# IMU_Layer_final.net
KiCad netlist of a schematic drawn in EAGLE
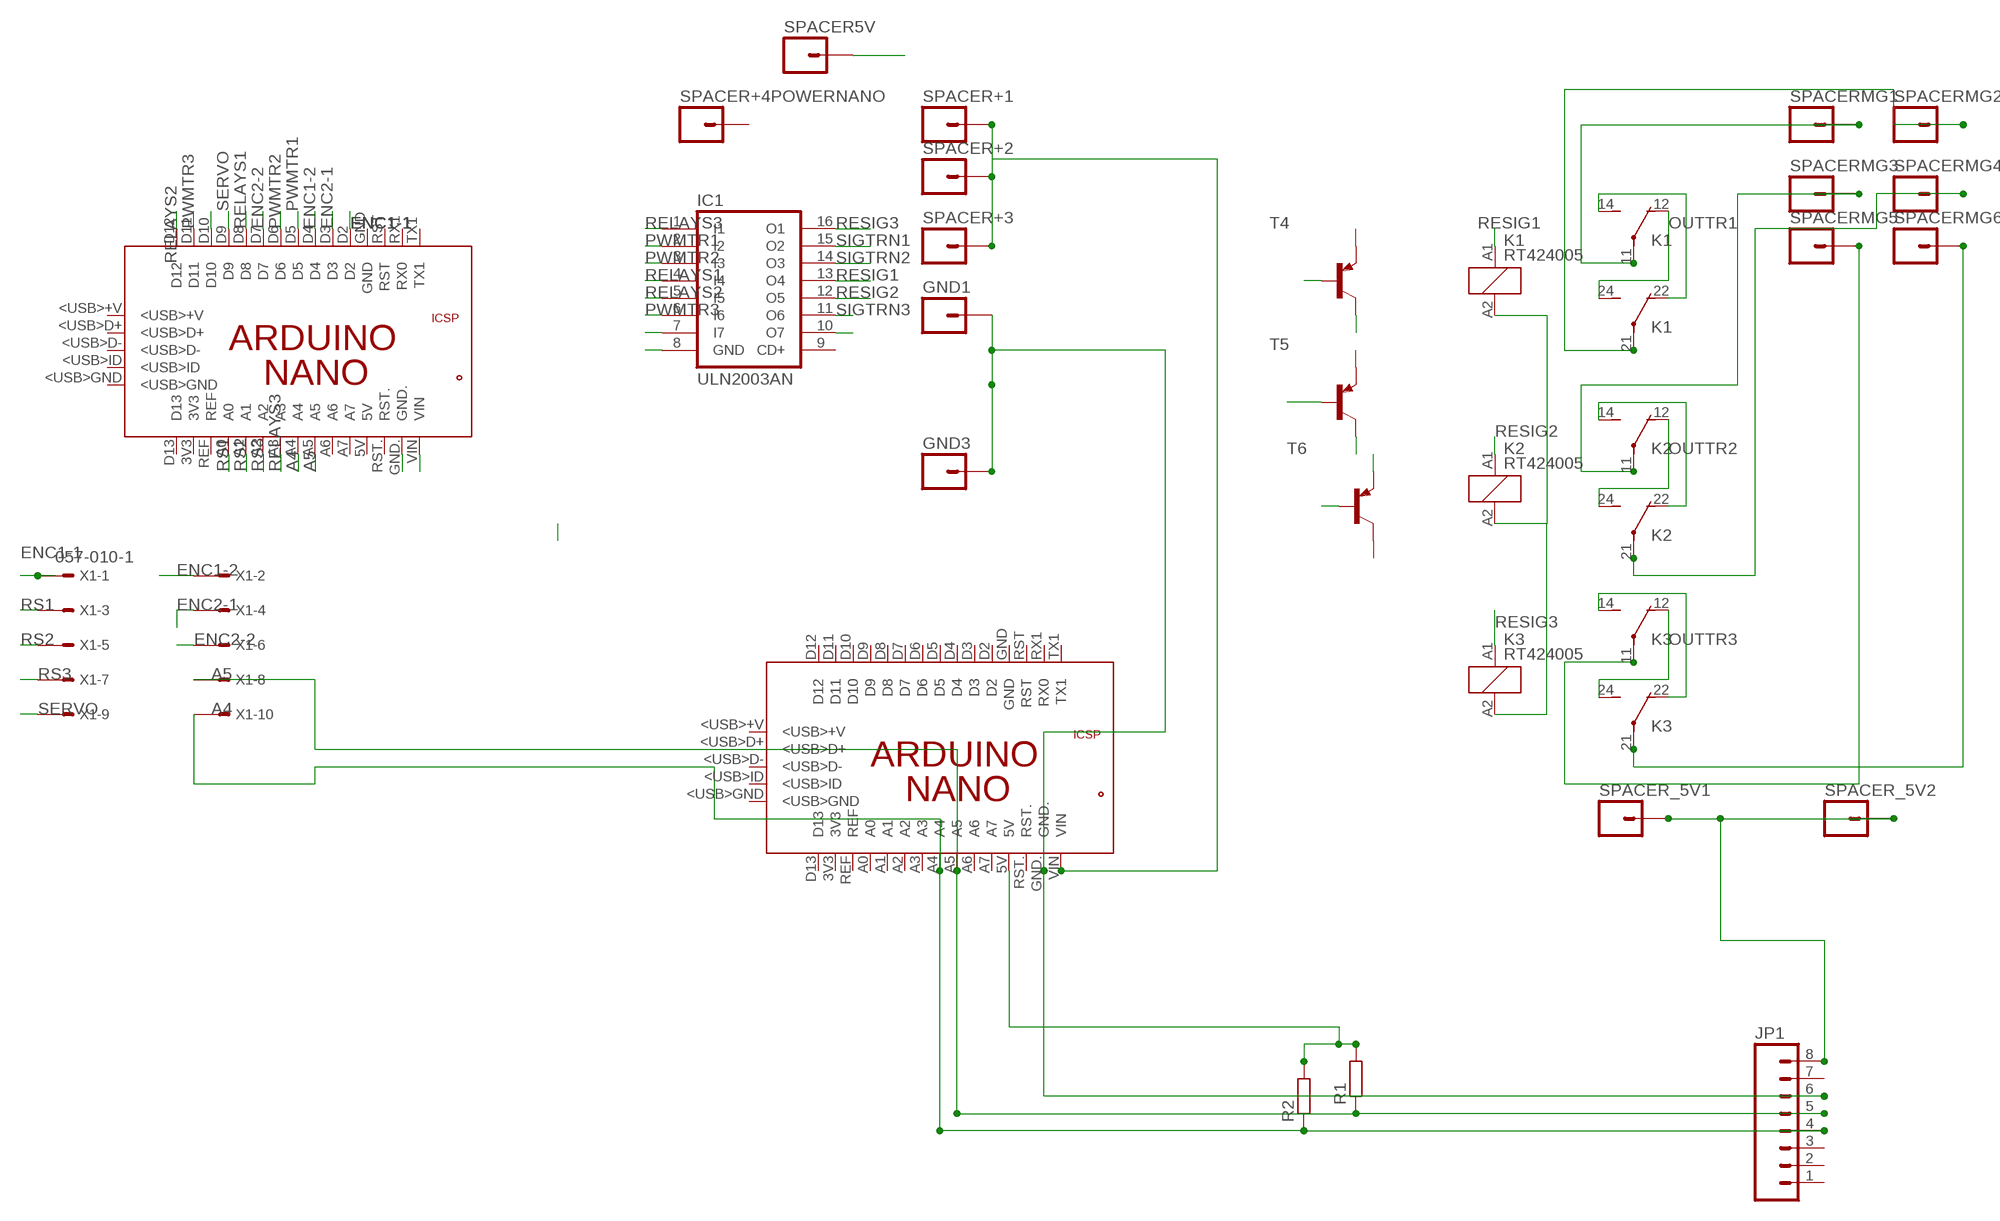
[diagram p0: schematic, sheet 1]

(export (version "E")
  (design (tool "Eeschema 10.0.6"))
  (components
    (comp (ref "GND1")
      (value "M01PTH_2MM")
      (footprint "eagle-import:1X01_2MM")
      (libsource (lib "eagle-import") (part "M01PTH_2MM"))
    )
    (comp (ref "GND3")
      (value "M01PTH_2MM")
      (footprint "eagle-import:1X01_2MM")
      (libsource (lib "eagle-import") (part "M01PTH_2MM"))
    )
    (comp (ref "IC1")
      (value "ULN2003AN")
      (footprint "eagle-import:DIL16")
      (libsource (lib "eagle-import") (part "ULN2003AN"))
    )
    (comp (ref "JP1")
      (value "M08LONGPADS")
      (footprint "eagle-import:1X08_LONGPADS")
      (libsource (lib "eagle-import") (part "M08LONGPADS"))
    )
    (comp (ref "K1")
      (value "RT424005")
      (footprint "eagle-import:RT2C_O")
      (libsource (lib "eagle-import") (part "RT42?4005"))
    )
    (comp (ref "K2")
      (value "RT424005")
      (footprint "eagle-import:RT2C_O")
      (libsource (lib "eagle-import") (part "RT42?4005"))
    )
    (comp (ref "K3")
      (value "RT424005")
      (footprint "eagle-import:RT2C_O")
      (libsource (lib "eagle-import") (part "RT42?4005"))
    )
    (comp (ref "PCB1")
      (value "ARDUINO_NANO")
      (footprint "eagle-import:ARDUINO_NANO")
      (libsource (lib "eagle-import") (part "ARDUINO_NANO"))
    )
    (comp (ref "PCB3")
      (value "ARDUINO_NANO")
      (footprint "eagle-import:ARDUINO_NANO")
      (libsource (lib "eagle-import") (part "ARDUINO_NANO"))
    )
    (comp (ref "R1")
      (value "R-EU_0207/12")
      (footprint "eagle-import:0207_12")
      (libsource (lib "eagle-import") (part "R-EU_0207/12"))
    )
    (comp (ref "R2")
      (value "R-EU_0207/12")
      (footprint "eagle-import:0207_12")
      (libsource (lib "eagle-import") (part "R-EU_0207/12"))
    )
    (comp (ref "SPACER+1")
      (value "M01PTH_2MM")
      (footprint "eagle-import:1X01_2MM")
      (libsource (lib "eagle-import") (part "M01PTH_2MM"))
    )
    (comp (ref "SPACER+2")
      (value "M01PTH_2MM")
      (footprint "eagle-import:1X01_2MM")
      (libsource (lib "eagle-import") (part "M01PTH_2MM"))
    )
    (comp (ref "SPACER+3")
      (value "M01PTH_2MM")
      (footprint "eagle-import:1X01_2MM")
      (libsource (lib "eagle-import") (part "M01PTH_2MM"))
    )
    (comp (ref "SPACER+4POWERNANO")
      (value "M01PTH_2MM")
      (footprint "eagle-import:1X01_2MM")
      (libsource (lib "eagle-import") (part "M01PTH_2MM"))
    )
    (comp (ref "SPACER5V")
      (value "M01PTH_2MM")
      (footprint "eagle-import:1X01_2MM")
      (libsource (lib "eagle-import") (part "M01PTH_2MM"))
    )
    (comp (ref "SPACERMG1")
      (value "M01PTH_2MM")
      (footprint "eagle-import:1X01_2MM")
      (libsource (lib "eagle-import") (part "M01PTH_2MM"))
    )
    (comp (ref "SPACERMG2")
      (value "M01PTH_2MM")
      (footprint "eagle-import:1X01_2MM")
      (libsource (lib "eagle-import") (part "M01PTH_2MM"))
    )
    (comp (ref "SPACERMG3")
      (value "M01PTH_2MM")
      (footprint "eagle-import:1X01_2MM")
      (libsource (lib "eagle-import") (part "M01PTH_2MM"))
    )
    (comp (ref "SPACERMG4")
      (value "M01PTH_2MM")
      (footprint "eagle-import:1X01_2MM")
      (libsource (lib "eagle-import") (part "M01PTH_2MM"))
    )
    (comp (ref "SPACERMG5")
      (value "M01PTH_2MM")
      (footprint "eagle-import:1X01_2MM")
      (libsource (lib "eagle-import") (part "M01PTH_2MM"))
    )
    (comp (ref "SPACERMG6")
      (value "M01PTH_2MM")
      (footprint "eagle-import:1X01_2MM")
      (libsource (lib "eagle-import") (part "M01PTH_2MM"))
    )
    (comp (ref "SPACER_5V1")
      (value "M01PTH_2MM")
      (footprint "eagle-import:1X01_2MM")
      (libsource (lib "eagle-import") (part "M01PTH_2MM"))
    )
    (comp (ref "SPACER_5V2")
      (value "M01PTH_2MM")
      (footprint "eagle-import:1X01_2MM")
      (libsource (lib "eagle-import") (part "M01PTH_2MM"))
    )
    (comp (ref "T4")
      (value "-PNP-TO218")
      (footprint "eagle-import:TO218")
      (libsource (lib "eagle-import") (part "-PNP-TO218"))
    )
    (comp (ref "T5")
      (value "-PNP-TO218")
      (footprint "eagle-import:TO218")
      (libsource (lib "eagle-import") (part "-PNP-TO218"))
    )
    (comp (ref "T6")
      (value "-PNP-TO218")
      (footprint "eagle-import:TO218")
      (libsource (lib "eagle-import") (part "-PNP-TO218"))
    )
    (comp (ref "X1")
      (value "057-010-1")
      (footprint "eagle-import:057-010-1")
      (libsource (lib "eagle-import") (part "057-010-1"))
    )
  )
  (nets
    (net (code "1") (name "/5V") (class "Default")
      (node (ref "JP1") (pin "8") (pinfunction "8_8") (pintype "passive"))
      (node (ref "SPACER5V") (pin "1") (pinfunction "1_1") (pintype "passive"))
      (node (ref "SPACER_5V1") (pin "1") (pinfunction "1_1") (pintype "passive"))
      (node (ref "SPACER_5V2") (pin "1") (pinfunction "1_1") (pintype "passive"))
    )
    (net (code "2") (name "/A4") (class "Default")
      (node (ref "JP1") (pin "4") (pinfunction "4_4") (pintype "passive"))
      (node (ref "PCB1") (pin "A4") (pinfunction "A4_A4") (pintype "bidirectional"))
      (node (ref "PCB3") (pin "A4") (pinfunction "A4_A4") (pintype "bidirectional"))
      (node (ref "R2") (pin "1") (pinfunction "1_1") (pintype "passive"))
      (node (ref "X1") (pin "10") (pinfunction "S_10") (pintype "passive"))
    )
    (net (code "3") (name "/A5") (class "Default")
      (node (ref "JP1") (pin "5") (pinfunction "5_5") (pintype "passive"))
      (node (ref "PCB1") (pin "A5") (pinfunction "A5_A5") (pintype "bidirectional"))
      (node (ref "PCB3") (pin "A5") (pinfunction "A5_A5") (pintype "bidirectional"))
      (node (ref "R1") (pin "1") (pinfunction "1_1") (pintype "passive"))
      (node (ref "X1") (pin "8") (pinfunction "S_8") (pintype "passive"))
    )
    (net (code "4") (name "/ENC1-1") (class "Default")
      (node (ref "PCB1") (pin "D2") (pinfunction "D2_D2") (pintype "bidirectional"))
      (node (ref "X1") (pin "1") (pinfunction "S_1") (pintype "passive"))
    )
    (net (code "5") (name "/ENC1-2") (class "Default")
      (node (ref "PCB1") (pin "D4") (pinfunction "D4_D4") (pintype "bidirectional"))
      (node (ref "X1") (pin "2") (pinfunction "S_2") (pintype "passive"))
    )
    (net (code "6") (name "/ENC2-1") (class "Default")
      (node (ref "PCB1") (pin "D3") (pinfunction "D3_D3") (pintype "bidirectional"))
      (node (ref "X1") (pin "4") (pinfunction "S_4") (pintype "passive"))
    )
    (net (code "7") (name "/ENC2-2") (class "Default")
      (node (ref "PCB1") (pin "D7") (pinfunction "D7_D7") (pintype "bidirectional"))
      (node (ref "X1") (pin "6") (pinfunction "S_6") (pintype "passive"))
    )
    (net (code "8") (name "/GND") (class "Default")
      (node (ref "GND1") (pin "1") (pinfunction "1_1") (pintype "passive"))
      (node (ref "GND3") (pin "1") (pinfunction "1_1") (pintype "passive"))
      (node (ref "IC1") (pin "8") (pinfunction "GND_8") (pintype "power_in"))
      (node (ref "JP1") (pin "6") (pinfunction "6_6") (pintype "passive"))
      (node (ref "PCB1") (pin "GND.") (pinfunction "GND._GND.") (pintype "bidirectional"))
      (node (ref "PCB3") (pin "GND.") (pinfunction "GND._GND.") (pintype "bidirectional"))
      (node (ref "T4") (pin "3") (pinfunction "E_3") (pintype "passive"))
      (node (ref "T5") (pin "3") (pinfunction "E_3") (pintype "passive"))
      (node (ref "T6") (pin "3") (pinfunction "E_3") (pintype "passive"))
    )
    (net (code "9") (name "/OUTTR1") (class "Default")
      (node (ref "K1") (pin "12") (pinfunction "O_12") (pintype "passive"))
      (node (ref "K1") (pin "24") (pinfunction "S_24") (pintype "passive"))
      (node (ref "T4") (pin "2") (pinfunction "C_2") (pintype "passive"))
    )
    (net (code "10") (name "/OUTTR2") (class "Default")
      (node (ref "K2") (pin "12") (pinfunction "O_12") (pintype "passive"))
      (node (ref "K2") (pin "24") (pinfunction "S_24") (pintype "passive"))
      (node (ref "T5") (pin "2") (pinfunction "C_2") (pintype "passive"))
    )
    (net (code "11") (name "/OUTTR3") (class "Default")
      (node (ref "K3") (pin "12") (pinfunction "O_12") (pintype "passive"))
      (node (ref "K3") (pin "24") (pinfunction "S_24") (pintype "passive"))
      (node (ref "T6") (pin "2") (pinfunction "C_2") (pintype "passive"))
    )
    (net (code "12") (name "/POWER") (class "Default")
      (node (ref "K1") (pin "14") (pinfunction "S_14") (pintype "passive"))
      (node (ref "K1") (pin "22") (pinfunction "O_22") (pintype "passive"))
      (node (ref "K1") (pin "A2") (pinfunction "2_A2") (pintype "passive"))
      (node (ref "K2") (pin "14") (pinfunction "S_14") (pintype "passive"))
      (node (ref "K2") (pin "22") (pinfunction "O_22") (pintype "passive"))
      (node (ref "K2") (pin "A2") (pinfunction "2_A2") (pintype "passive"))
      (node (ref "K3") (pin "14") (pinfunction "S_14") (pintype "passive"))
      (node (ref "K3") (pin "22") (pinfunction "O_22") (pintype "passive"))
      (node (ref "K3") (pin "A2") (pinfunction "2_A2") (pintype "passive"))
      (node (ref "PCB1") (pin "VIN") (pinfunction "VIN_VIN") (pintype "bidirectional"))
      (node (ref "PCB3") (pin "VIN") (pinfunction "VIN_VIN") (pintype "bidirectional"))
      (node (ref "SPACER+1") (pin "1") (pinfunction "1_1") (pintype "passive"))
      (node (ref "SPACER+2") (pin "1") (pinfunction "1_1") (pintype "passive"))
      (node (ref "SPACER+3") (pin "1") (pinfunction "1_1") (pintype "passive"))
    )
    (net (code "13") (name "/PWMTR1") (class "Default")
      (node (ref "IC1") (pin "2") (pinfunction "I2_2") (pintype "input"))
      (node (ref "PCB1") (pin "D5") (pinfunction "D5_D5") (pintype "bidirectional"))
    )
    (net (code "14") (name "/PWMTR2") (class "Default")
      (node (ref "IC1") (pin "3") (pinfunction "I3_3") (pintype "input"))
      (node (ref "PCB1") (pin "D6") (pinfunction "D6_D6") (pintype "bidirectional"))
    )
    (net (code "15") (name "/PWMTR3") (class "Default")
      (node (ref "IC1") (pin "6") (pinfunction "I6_6") (pintype "input"))
      (node (ref "PCB1") (pin "D11") (pinfunction "D11_D11") (pintype "bidirectional"))
    )
    (net (code "16") (name "/RELAYS1") (class "Default")
      (node (ref "IC1") (pin "4") (pinfunction "I4_4") (pintype "input"))
      (node (ref "PCB1") (pin "D8") (pinfunction "D8_D8") (pintype "bidirectional"))
    )
    (net (code "17") (name "/RELAYS2") (class "Default")
      (node (ref "IC1") (pin "5") (pinfunction "I5_5") (pintype "input"))
      (node (ref "PCB1") (pin "D12") (pinfunction "D12_D12") (pintype "bidirectional"))
    )
    (net (code "18") (name "/RELAYS3") (class "Default")
      (node (ref "IC1") (pin "1") (pinfunction "I1_1") (pintype "input"))
      (node (ref "PCB1") (pin "A3") (pinfunction "A3_A3") (pintype "bidirectional"))
    )
    (net (code "19") (name "/RESIG1") (class "Default")
      (node (ref "IC1") (pin "13") (pinfunction "O4_13") (pintype "open_collector"))
      (node (ref "K1") (pin "A1") (pinfunction "1_A1") (pintype "passive"))
    )
    (net (code "20") (name "/RESIG2") (class "Default")
      (node (ref "IC1") (pin "12") (pinfunction "O5_12") (pintype "open_collector"))
      (node (ref "K2") (pin "A1") (pinfunction "1_A1") (pintype "passive"))
    )
    (net (code "21") (name "/RESIG3") (class "Default")
      (node (ref "IC1") (pin "16") (pinfunction "O1_16") (pintype "open_collector"))
      (node (ref "K3") (pin "A1") (pinfunction "1_A1") (pintype "passive"))
    )
    (net (code "22") (name "/RS1") (class "Default")
      (node (ref "PCB1") (pin "A0") (pinfunction "A0_A0") (pintype "bidirectional"))
      (node (ref "X1") (pin "3") (pinfunction "S_3") (pintype "passive"))
    )
    (net (code "23") (name "/RS2") (class "Default")
      (node (ref "PCB1") (pin "A1") (pinfunction "A1_A1") (pintype "bidirectional"))
      (node (ref "X1") (pin "5") (pinfunction "S_5") (pintype "passive"))
    )
    (net (code "24") (name "/RS3") (class "Default")
      (node (ref "PCB1") (pin "A2") (pinfunction "A2_A2") (pintype "bidirectional"))
      (node (ref "X1") (pin "7") (pinfunction "S_7") (pintype "passive"))
    )
    (net (code "25") (name "/SERVO") (class "Default")
      (node (ref "PCB1") (pin "D9") (pinfunction "D9_D9") (pintype "bidirectional"))
      (node (ref "X1") (pin "9") (pinfunction "S_9") (pintype "passive"))
    )
    (net (code "26") (name "/SIGTRN1") (class "Default")
      (node (ref "IC1") (pin "15") (pinfunction "O2_15") (pintype "open_collector"))
      (node (ref "T4") (pin "1") (pinfunction "B_1") (pintype "passive"))
    )
    (net (code "27") (name "/SIGTRN2") (class "Default")
      (node (ref "IC1") (pin "14") (pinfunction "O3_14") (pintype "open_collector"))
      (node (ref "T5") (pin "1") (pinfunction "B_1") (pintype "passive"))
    )
    (net (code "28") (name "/SIGTRN3") (class "Default")
      (node (ref "IC1") (pin "11") (pinfunction "O6_11") (pintype "open_collector"))
      (node (ref "T6") (pin "1") (pinfunction "B_1") (pintype "passive"))
    )
    (net (code "29") (name "Net-(K1B-P)") (class "Default")
      (node (ref "K1") (pin "11") (pinfunction "P_11") (pintype "passive"))
      (node (ref "SPACERMG1") (pin "1") (pinfunction "1_1") (pintype "passive"))
    )
    (net (code "30") (name "Net-(K1C-P)") (class "Default")
      (node (ref "K1") (pin "21") (pinfunction "P_21") (pintype "passive"))
      (node (ref "SPACERMG2") (pin "1") (pinfunction "1_1") (pintype "passive"))
    )
    (net (code "31") (name "Net-(K2B-P)") (class "Default")
      (node (ref "K2") (pin "11") (pinfunction "P_11") (pintype "passive"))
      (node (ref "SPACERMG3") (pin "1") (pinfunction "1_1") (pintype "passive"))
    )
    (net (code "32") (name "Net-(K2C-P)") (class "Default")
      (node (ref "K2") (pin "21") (pinfunction "P_21") (pintype "passive"))
      (node (ref "SPACERMG4") (pin "1") (pinfunction "1_1") (pintype "passive"))
    )
    (net (code "33") (name "Net-(K3B-P)") (class "Default")
      (node (ref "K3") (pin "11") (pinfunction "P_11") (pintype "passive"))
      (node (ref "SPACERMG5") (pin "1") (pinfunction "1_1") (pintype "passive"))
    )
    (net (code "34") (name "Net-(K3C-P)") (class "Default")
      (node (ref "K3") (pin "21") (pinfunction "P_21") (pintype "passive"))
      (node (ref "SPACERMG6") (pin "1") (pinfunction "1_1") (pintype "passive"))
    )
    (net (code "35") (name "Net-(PCB3-Pad5V)") (class "Default")
      (node (ref "PCB3") (pin "5V") (pinfunction "5V_5V") (pintype "bidirectional"))
      (node (ref "R1") (pin "2") (pinfunction "2_2") (pintype "passive"))
      (node (ref "R2") (pin "2") (pinfunction "2_2") (pintype "passive"))
    )
    (net (code "36") (name "unconnected-(IC1-CD+-Pad9)") (class "Default")
      (node (ref "IC1") (pin "9") (pinfunction "CD+_9") (pintype "passive"))
    )
    (net (code "37") (name "unconnected-(IC1-I7-Pad7)") (class "Default")
      (node (ref "IC1") (pin "7") (pinfunction "I7_7") (pintype "input"))
    )
    (net (code "38") (name "unconnected-(IC1-O7-Pad10)") (class "Default")
      (node (ref "IC1") (pin "10") (pinfunction "O7_10") (pintype "open_collector"))
    )
    (net (code "39") (name "unconnected-(JP1-Pad1)") (class "Default")
      (node (ref "JP1") (pin "1") (pinfunction "1_1") (pintype "passive"))
    )
    (net (code "40") (name "unconnected-(JP1-Pad2)") (class "Default")
      (node (ref "JP1") (pin "2") (pinfunction "2_2") (pintype "passive"))
    )
    (net (code "41") (name "unconnected-(JP1-Pad3)") (class "Default")
      (node (ref "JP1") (pin "3") (pinfunction "3_3") (pintype "passive"))
    )
    (net (code "42") (name "unconnected-(JP1-Pad7)") (class "Default")
      (node (ref "JP1") (pin "7") (pinfunction "7_7") (pintype "passive"))
    )
    (net (code "43") (name "unconnected-(PCB1-Pad3V3)") (class "Default")
      (node (ref "PCB1") (pin "3V3") (pinfunction "3V3_3V3") (pintype "bidirectional"))
    )
    (net (code "44") (name "unconnected-(PCB1-Pad5V)") (class "Default")
      (node (ref "PCB1") (pin "5V") (pinfunction "5V_5V") (pintype "bidirectional"))
    )
    (net (code "45") (name "unconnected-(PCB1-Pad5V.)") (class "Default")
      (node (ref "PCB1") (pin "5V.") (pinfunction "5V._5V.") (pintype "bidirectional"))
    )
    (net (code "46") (name "unconnected-(PCB1-Pad<USB>+V)") (class "Default")
      (node (ref "PCB1") (pin "<USB>+V") (pinfunction "<USB>+V_<USB>+V") (pintype "bidirectional"))
    )
    (net (code "47") (name "unconnected-(PCB1-Pad<USB>D+)") (class "Default")
      (node (ref "PCB1") (pin "<USB>D+") (pinfunction "<USB>D+_<USB>D+") (pintype "bidirectional"))
    )
    (net (code "48") (name "unconnected-(PCB1-Pad<USB>D-)") (class "Default")
      (node (ref "PCB1") (pin "<USB>D-") (pinfunction "<USB>D-_<USB>D-") (pintype "bidirectional"))
    )
    (net (code "49") (name "unconnected-(PCB1-Pad<USB>GND)") (class "Default")
      (node (ref "PCB1") (pin "<USB>GND") (pinfunction "<USB>GND_<USB>GND") (pintype "bidirectional"))
    )
    (net (code "50") (name "unconnected-(PCB1-Pad<USB>ID)") (class "Default")
      (node (ref "PCB1") (pin "<USB>ID") (pinfunction "<USB>ID_<USB>ID") (pintype "bidirectional"))
    )
    (net (code "51") (name "unconnected-(PCB1-PadA6)") (class "Default")
      (node (ref "PCB1") (pin "A6") (pinfunction "A6_A6") (pintype "bidirectional"))
    )
    (net (code "52") (name "unconnected-(PCB1-PadA7)") (class "Default")
      (node (ref "PCB1") (pin "A7") (pinfunction "A7_A7") (pintype "bidirectional"))
    )
    (net (code "53") (name "unconnected-(PCB1-PadD10)") (class "Default")
      (node (ref "PCB1") (pin "D10") (pinfunction "D10_D10") (pintype "bidirectional"))
    )
    (net (code "54") (name "unconnected-(PCB1-PadD13)") (class "Default")
      (node (ref "PCB1") (pin "D13") (pinfunction "D13_D13") (pintype "bidirectional"))
    )
    (net (code "55") (name "unconnected-(PCB1-PadGND)") (class "Default")
      (node (ref "PCB1") (pin "GND") (pinfunction "GND_GND") (pintype "bidirectional"))
    )
    (net (code "56") (name "unconnected-(PCB1-PadGND_)") (class "Default")
      (node (ref "PCB1") (pin "GND_") (pinfunction "GND__GND_") (pintype "bidirectional"))
    )
    (net (code "57") (name "unconnected-(PCB1-PadMISO)") (class "Default")
      (node (ref "PCB1") (pin "MISO") (pinfunction "MISO_MISO") (pintype "bidirectional"))
    )
    (net (code "58") (name "unconnected-(PCB1-PadMOSI)") (class "Default")
      (node (ref "PCB1") (pin "MOSI") (pinfunction "MOSI_MOSI") (pintype "bidirectional"))
    )
    (net (code "59") (name "unconnected-(PCB1-PadREF)") (class "Default")
      (node (ref "PCB1") (pin "REF") (pinfunction "REF_REF") (pintype "bidirectional"))
    )
    (net (code "60") (name "unconnected-(PCB1-PadRESET..)") (class "Default")
      (node (ref "PCB1") (pin "RESET..") (pinfunction "RESET.._RESET..") (pintype "bidirectional"))
    )
    (net (code "61") (name "unconnected-(PCB1-PadRST)") (class "Default")
      (node (ref "PCB1") (pin "RST") (pinfunction "RST_RST") (pintype "bidirectional"))
    )
    (net (code "62") (name "unconnected-(PCB1-PadRST.)") (class "Default")
      (node (ref "PCB1") (pin "RST.") (pinfunction "RST._RST.") (pintype "bidirectional"))
    )
    (net (code "63") (name "unconnected-(PCB1-PadSCK)") (class "Default")
      (node (ref "PCB1") (pin "SCK") (pinfunction "SCK_SCK") (pintype "bidirectional"))
    )
    (net (code "64") (name "unconnected-(PCB1-PadTX1)") (class "Default")
      (node (ref "PCB1") (pin "TX1") (pinfunction "TX1_TX1") (pintype "bidirectional"))
    )
    (net (code "65") (name "unconnected-(PCB1-RX0-PadRX1)") (class "Default")
      (node (ref "PCB1") (pin "RX1") (pinfunction "RX0_RX1") (pintype "bidirectional"))
    )
    (net (code "66") (name "unconnected-(PCB3-Pad3V3)") (class "Default")
      (node (ref "PCB3") (pin "3V3") (pinfunction "3V3_3V3") (pintype "bidirectional"))
    )
    (net (code "67") (name "unconnected-(PCB3-Pad5V.)") (class "Default")
      (node (ref "PCB3") (pin "5V.") (pinfunction "5V._5V.") (pintype "bidirectional"))
    )
    (net (code "68") (name "unconnected-(PCB3-Pad<USB>+V)") (class "Default")
      (node (ref "PCB3") (pin "<USB>+V") (pinfunction "<USB>+V_<USB>+V") (pintype "bidirectional"))
    )
    (net (code "69") (name "unconnected-(PCB3-Pad<USB>D+)") (class "Default")
      (node (ref "PCB3") (pin "<USB>D+") (pinfunction "<USB>D+_<USB>D+") (pintype "bidirectional"))
    )
    (net (code "70") (name "unconnected-(PCB3-Pad<USB>D-)") (class "Default")
      (node (ref "PCB3") (pin "<USB>D-") (pinfunction "<USB>D-_<USB>D-") (pintype "bidirectional"))
    )
    (net (code "71") (name "unconnected-(PCB3-Pad<USB>GND)") (class "Default")
      (node (ref "PCB3") (pin "<USB>GND") (pinfunction "<USB>GND_<USB>GND") (pintype "bidirectional"))
    )
    (net (code "72") (name "unconnected-(PCB3-Pad<USB>ID)") (class "Default")
      (node (ref "PCB3") (pin "<USB>ID") (pinfunction "<USB>ID_<USB>ID") (pintype "bidirectional"))
    )
    (net (code "73") (name "unconnected-(PCB3-PadA0)") (class "Default")
      (node (ref "PCB3") (pin "A0") (pinfunction "A0_A0") (pintype "bidirectional"))
    )
    (net (code "74") (name "unconnected-(PCB3-PadA1)") (class "Default")
      (node (ref "PCB3") (pin "A1") (pinfunction "A1_A1") (pintype "bidirectional"))
    )
    (net (code "75") (name "unconnected-(PCB3-PadA2)") (class "Default")
      (node (ref "PCB3") (pin "A2") (pinfunction "A2_A2") (pintype "bidirectional"))
    )
    (net (code "76") (name "unconnected-(PCB3-PadA3)") (class "Default")
      (node (ref "PCB3") (pin "A3") (pinfunction "A3_A3") (pintype "bidirectional"))
    )
    (net (code "77") (name "unconnected-(PCB3-PadA6)") (class "Default")
      (node (ref "PCB3") (pin "A6") (pinfunction "A6_A6") (pintype "bidirectional"))
    )
    (net (code "78") (name "unconnected-(PCB3-PadA7)") (class "Default")
      (node (ref "PCB3") (pin "A7") (pinfunction "A7_A7") (pintype "bidirectional"))
    )
    (net (code "79") (name "unconnected-(PCB3-PadD2)") (class "Default")
      (node (ref "PCB3") (pin "D2") (pinfunction "D2_D2") (pintype "bidirectional"))
    )
    (net (code "80") (name "unconnected-(PCB3-PadD3)") (class "Default")
      (node (ref "PCB3") (pin "D3") (pinfunction "D3_D3") (pintype "bidirectional"))
    )
    (net (code "81") (name "unconnected-(PCB3-PadD4)") (class "Default")
      (node (ref "PCB3") (pin "D4") (pinfunction "D4_D4") (pintype "bidirectional"))
    )
    (net (code "82") (name "unconnected-(PCB3-PadD5)") (class "Default")
      (node (ref "PCB3") (pin "D5") (pinfunction "D5_D5") (pintype "bidirectional"))
    )
    (net (code "83") (name "unconnected-(PCB3-PadD6)") (class "Default")
      (node (ref "PCB3") (pin "D6") (pinfunction "D6_D6") (pintype "bidirectional"))
    )
    (net (code "84") (name "unconnected-(PCB3-PadD7)") (class "Default")
      (node (ref "PCB3") (pin "D7") (pinfunction "D7_D7") (pintype "bidirectional"))
    )
    (net (code "85") (name "unconnected-(PCB3-PadD8)") (class "Default")
      (node (ref "PCB3") (pin "D8") (pinfunction "D8_D8") (pintype "bidirectional"))
    )
    (net (code "86") (name "unconnected-(PCB3-PadD9)") (class "Default")
      (node (ref "PCB3") (pin "D9") (pinfunction "D9_D9") (pintype "bidirectional"))
    )
    (net (code "87") (name "unconnected-(PCB3-PadD10)") (class "Default")
      (node (ref "PCB3") (pin "D10") (pinfunction "D10_D10") (pintype "bidirectional"))
    )
    (net (code "88") (name "unconnected-(PCB3-PadD11)") (class "Default")
      (node (ref "PCB3") (pin "D11") (pinfunction "D11_D11") (pintype "bidirectional"))
    )
    (net (code "89") (name "unconnected-(PCB3-PadD12)") (class "Default")
      (node (ref "PCB3") (pin "D12") (pinfunction "D12_D12") (pintype "bidirectional"))
    )
    (net (code "90") (name "unconnected-(PCB3-PadD13)") (class "Default")
      (node (ref "PCB3") (pin "D13") (pinfunction "D13_D13") (pintype "bidirectional"))
    )
    (net (code "91") (name "unconnected-(PCB3-PadGND)") (class "Default")
      (node (ref "PCB3") (pin "GND") (pinfunction "GND_GND") (pintype "bidirectional"))
    )
    (net (code "92") (name "unconnected-(PCB3-PadGND_)") (class "Default")
      (node (ref "PCB3") (pin "GND_") (pinfunction "GND__GND_") (pintype "bidirectional"))
    )
    (net (code "93") (name "unconnected-(PCB3-PadMISO)") (class "Default")
      (node (ref "PCB3") (pin "MISO") (pinfunction "MISO_MISO") (pintype "bidirectional"))
    )
    (net (code "94") (name "unconnected-(PCB3-PadMOSI)") (class "Default")
      (node (ref "PCB3") (pin "MOSI") (pinfunction "MOSI_MOSI") (pintype "bidirectional"))
    )
    (net (code "95") (name "unconnected-(PCB3-PadREF)") (class "Default")
      (node (ref "PCB3") (pin "REF") (pinfunction "REF_REF") (pintype "bidirectional"))
    )
    (net (code "96") (name "unconnected-(PCB3-PadRESET..)") (class "Default")
      (node (ref "PCB3") (pin "RESET..") (pinfunction "RESET.._RESET..") (pintype "bidirectional"))
    )
    (net (code "97") (name "unconnected-(PCB3-PadRST)") (class "Default")
      (node (ref "PCB3") (pin "RST") (pinfunction "RST_RST") (pintype "bidirectional"))
    )
    (net (code "98") (name "unconnected-(PCB3-PadRST.)") (class "Default")
      (node (ref "PCB3") (pin "RST.") (pinfunction "RST._RST.") (pintype "bidirectional"))
    )
    (net (code "99") (name "unconnected-(PCB3-PadSCK)") (class "Default")
      (node (ref "PCB3") (pin "SCK") (pinfunction "SCK_SCK") (pintype "bidirectional"))
    )
    (net (code "100") (name "unconnected-(PCB3-PadTX1)") (class "Default")
      (node (ref "PCB3") (pin "TX1") (pinfunction "TX1_TX1") (pintype "bidirectional"))
    )
    (net (code "101") (name "unconnected-(PCB3-RX0-PadRX1)") (class "Default")
      (node (ref "PCB3") (pin "RX1") (pinfunction "RX0_RX1") (pintype "bidirectional"))
    )
    (net (code "102") (name "unconnected-(SPACER+4POWERNANO-Pad1)") (class "Default")
      (node (ref "SPACER+4POWERNANO") (pin "1") (pinfunction "1_1") (pintype "passive"))
    )
  )
)
